# etchasketch.net
KiCad netlist of a schematic drawn in EAGLE
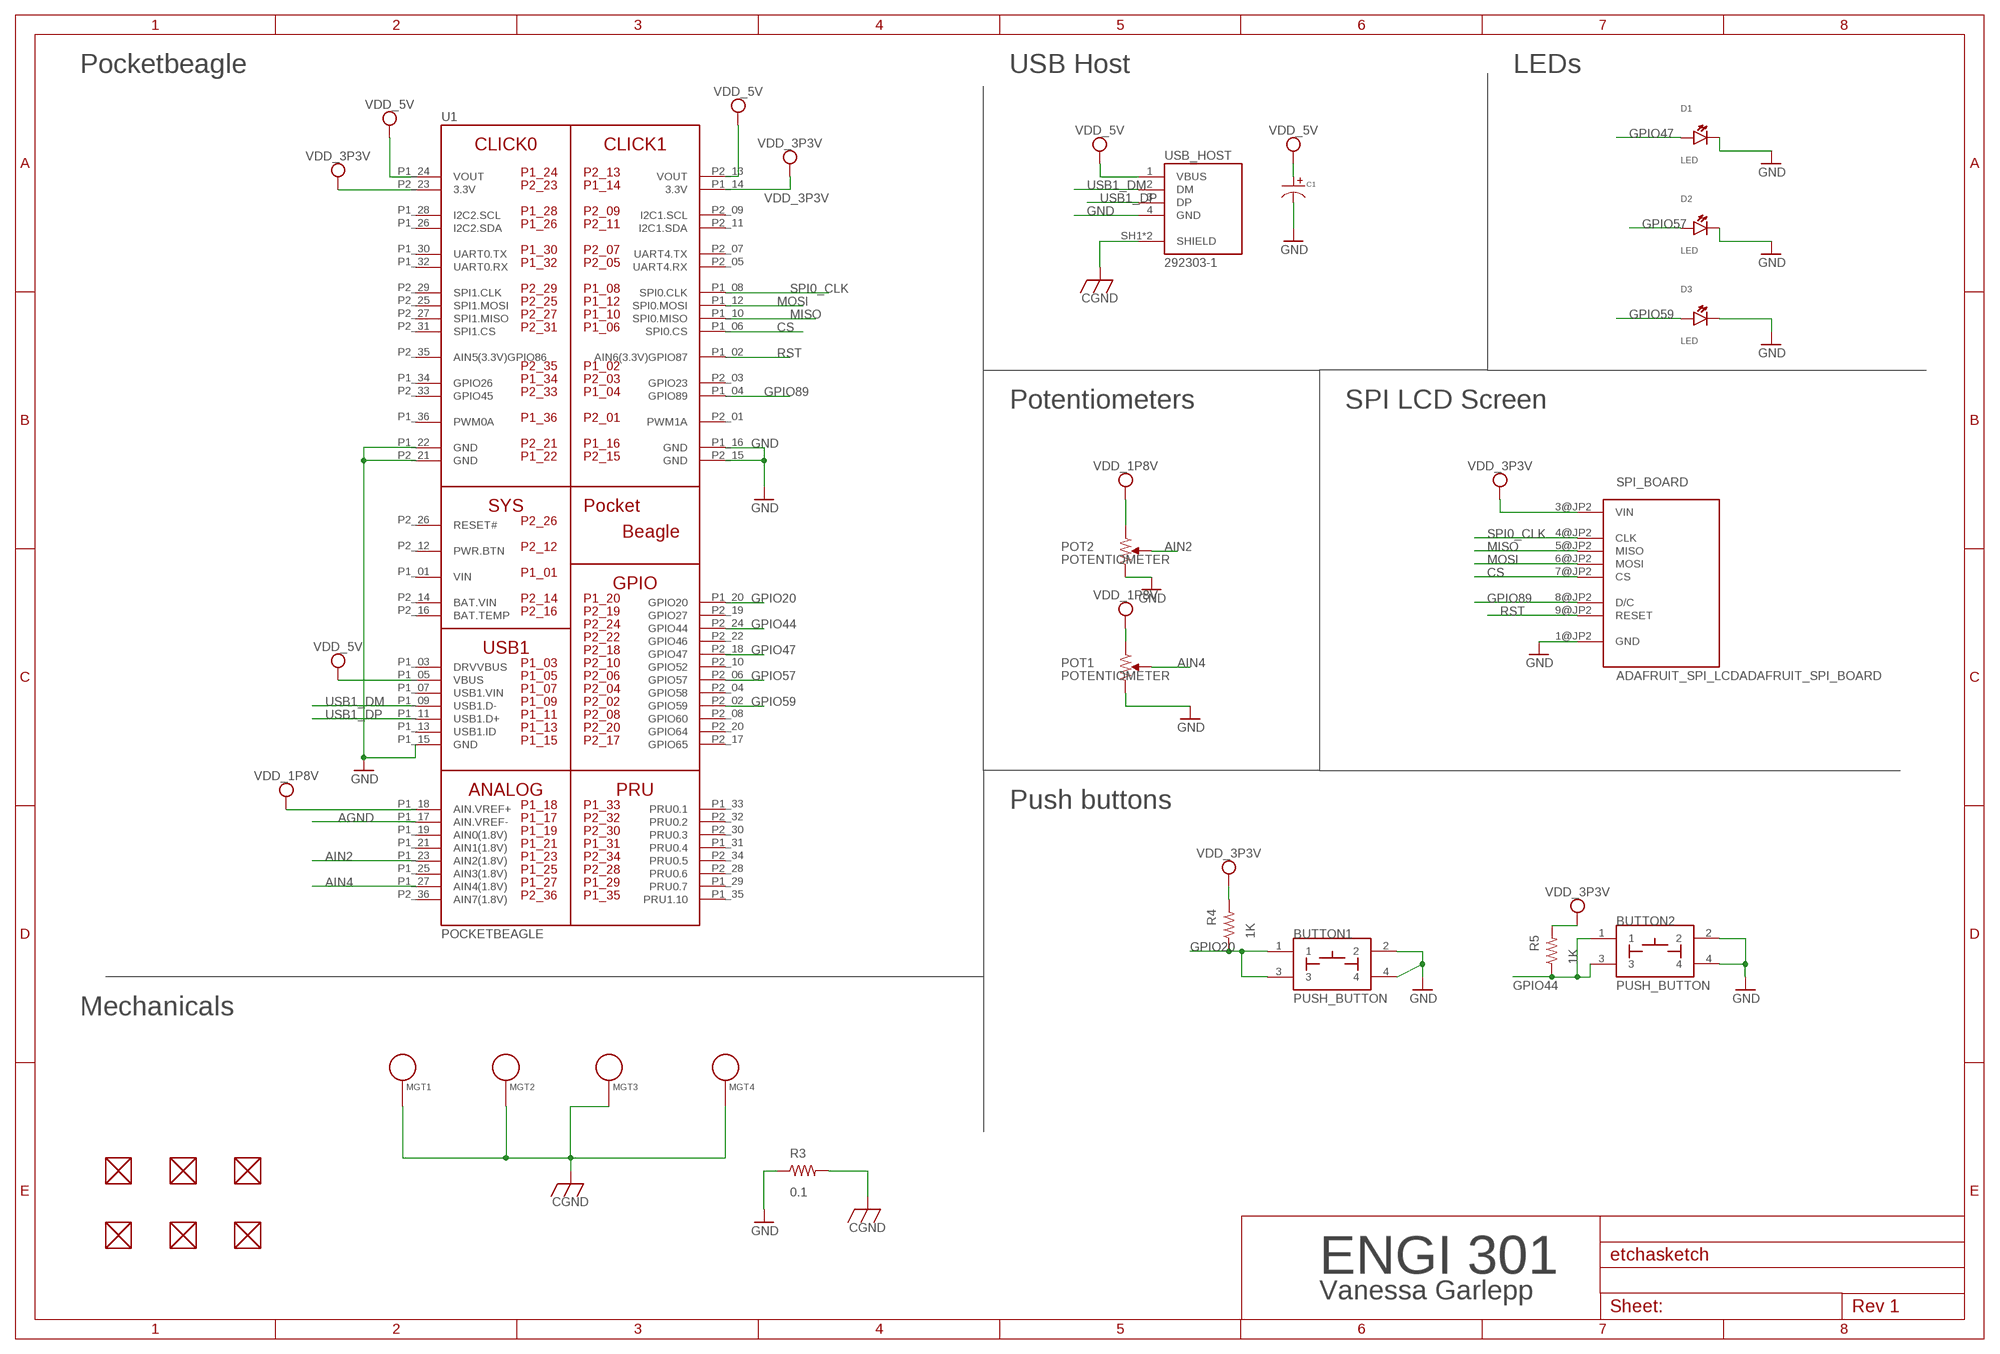
[diagram p0: schematic, sheet 1]

(export (version "E")
  (design (tool "Eeschema 10.0.6"))
  (components
    (comp (ref "BUTTON1")
      (value "PUSH_BUTTON")
      (footprint "eagle-import:BUTTON_12.5MM")
      (libsource (lib "eagle-import") (part "PUSH_BUTTON"))
    )
    (comp (ref "BUTTON2")
      (value "PUSH_BUTTON")
      (footprint "eagle-import:BUTTON_12.5MM")
      (libsource (lib "eagle-import") (part "PUSH_BUTTON"))
    )
    (comp (ref "C1")
      (value "CAPACITOR_P_10MM")
      (footprint "eagle-import:CP10MM")
      (libsource (lib "eagle-import") (part "CAPACITOR_P_10MM"))
    )
    (comp (ref "D1")
      (value "LED")
      (footprint "eagle-import:EIA-STD")
      (libsource (lib "eagle-import") (part "LED"))
    )
    (comp (ref "D2")
      (value "LED")
      (footprint "eagle-import:EIA-STD")
      (libsource (lib "eagle-import") (part "LED"))
    )
    (comp (ref "D3")
      (value "LED")
      (footprint "eagle-import:EIA-STD")
      (libsource (lib "eagle-import") (part "LED"))
    )
    (comp (ref "FUD1")
      (value "FIDUCIAL")
      (footprint "eagle-import:FIDUCIAL_40MIL")
      (libsource (lib "eagle-import") (part "FIDUCIAL"))
    )
    (comp (ref "FUD2")
      (value "FIDUCIAL")
      (footprint "eagle-import:FIDUCIAL_40MIL")
      (libsource (lib "eagle-import") (part "FIDUCIAL"))
    )
    (comp (ref "FUD3")
      (value "FIDUCIAL")
      (footprint "eagle-import:FIDUCIAL_40MIL")
      (libsource (lib "eagle-import") (part "FIDUCIAL"))
    )
    (comp (ref "FUD4")
      (value "FIDUCIAL")
      (footprint "eagle-import:FIDUCIAL_40MIL")
      (libsource (lib "eagle-import") (part "FIDUCIAL"))
    )
    (comp (ref "FUD5")
      (value "FIDUCIAL")
      (footprint "eagle-import:FIDUCIAL_40MIL")
      (libsource (lib "eagle-import") (part "FIDUCIAL"))
    )
    (comp (ref "FUD6")
      (value "FIDUCIAL")
      (footprint "eagle-import:FIDUCIAL_40MIL")
      (libsource (lib "eagle-import") (part "FIDUCIAL"))
    )
    (comp (ref "MGT1")
      (value "MOUNTING_HOLE")
      (footprint "eagle-import:MOUNTING_HOLE")
      (libsource (lib "eagle-import") (part "MOUNTING_HOLE"))
    )
    (comp (ref "MGT2")
      (value "MOUNTING_HOLE")
      (footprint "eagle-import:MOUNTING_HOLE")
      (libsource (lib "eagle-import") (part "MOUNTING_HOLE"))
    )
    (comp (ref "MGT3")
      (value "MOUNTING_HOLE")
      (footprint "eagle-import:MOUNTING_HOLE")
      (libsource (lib "eagle-import") (part "MOUNTING_HOLE"))
    )
    (comp (ref "MGT4")
      (value "MOUNTING_HOLE")
      (footprint "eagle-import:MOUNTING_HOLE")
      (libsource (lib "eagle-import") (part "MOUNTING_HOLE"))
    )
    (comp (ref "POT1")
      (value "POTENTIOMETER")
      (footprint "eagle-import:POT-PO90S")
      (libsource (lib "eagle-import") (part "POTENTIOMETER"))
    )
    (comp (ref "POT2")
      (value "POTENTIOMETER")
      (footprint "eagle-import:POT-PO90S")
      (libsource (lib "eagle-import") (part "POTENTIOMETER"))
    )
    (comp (ref "R3")
      (value "0.1")
      (footprint "eagle-import:R0603")
      (libsource (lib "eagle-import") (part "R_R0603"))
    )
    (comp (ref "R4")
      (value "1K")
      (footprint "eagle-import:R0402")
      (libsource (lib "eagle-import") (part "R_R0402"))
    )
    (comp (ref "R5")
      (value "1K")
      (footprint "eagle-import:R0402")
      (libsource (lib "eagle-import") (part "R_R0402"))
    )
    (comp (ref "SPI_BOARD")
      (value "ADAFRUIT_SPI_LCDADAFRUIT_SPI_BOARD")
      (footprint "eagle-import:ADAFRUIT_SPI_BOARD")
      (libsource (lib "eagle-import") (part "ADAFRUIT_SPI_LCDADAFRUIT_SPI_BOARD"))
    )
    (comp (ref "U1")
      (value "POCKETBEAGLE")
      (footprint "eagle-import:POCKETBEAGLE")
      (libsource (lib "eagle-import") (part "POCKETBEAGLE"))
    )
    (comp (ref "USB_HOST")
      (value "292303-1")
      (footprint "eagle-import:TE_292303-1")
      (fields (field (name "MF") "TE Connectivity"))
      (libsource (lib "eagle-import") (part "292303-1"))
    )
  )
  (nets
    (net (code "1") (name "/AGND") (class "Default")
      (node (ref "U1") (pin "P1_17") (pinfunction "AIN.VREF-_P1_17") (pintype "input"))
    )
    (net (code "2") (name "/AIN2") (class "Default")
      (node (ref "POT2") (pin "S") (pinfunction "S_S") (pintype "bidirectional"))
      (node (ref "U1") (pin "P1_23") (pinfunction "AIN2(1.8V)_P1_23") (pintype "input"))
    )
    (net (code "3") (name "/AIN4") (class "Default")
      (node (ref "POT1") (pin "S") (pinfunction "S_S") (pintype "bidirectional"))
      (node (ref "U1") (pin "P1_27") (pinfunction "AIN4(1.8V)_P1_27") (pintype "input"))
    )
    (net (code "4") (name "/BAT.VIN") (class "Default")
      (node (ref "U1") (pin "P2_14") (pinfunction "BAT.VIN_P2_14") (pintype "power_in"))
    )
    (net (code "5") (name "/CS") (class "Default")
      (node (ref "SPI_BOARD") (pin "7@JP2") (pinfunction "CS_7@JP2") (pintype "bidirectional"))
      (node (ref "U1") (pin "P1_06") (pinfunction "SPI0.CS_P1_06") (pintype "bidirectional"))
    )
    (net (code "6") (name "/GPIO20") (class "Default")
      (node (ref "BUTTON1") (pin "1") (pinfunction "1_1") (pintype "bidirectional"))
      (node (ref "BUTTON1") (pin "3") (pinfunction "3_3") (pintype "bidirectional"))
      (node (ref "R4") (pin "1") (pinfunction "1_1") (pintype "passive"))
      (node (ref "U1") (pin "P1_20") (pinfunction "GPIO20_P1_20") (pintype "bidirectional"))
    )
    (net (code "7") (name "/GPIO44") (class "Default")
      (node (ref "BUTTON2") (pin "1") (pinfunction "1_1") (pintype "bidirectional"))
      (node (ref "BUTTON2") (pin "3") (pinfunction "3_3") (pintype "bidirectional"))
      (node (ref "R5") (pin "1") (pinfunction "1_1") (pintype "passive"))
      (node (ref "U1") (pin "P2_24") (pinfunction "GPIO44_P2_24") (pintype "bidirectional"))
    )
    (net (code "8") (name "/GPIO47") (class "Default")
      (node (ref "D1") (pin "ANODE") (pinfunction "ANODE_ANODE") (pintype "bidirectional"))
      (node (ref "U1") (pin "P2_18") (pinfunction "GPIO47_P2_18") (pintype "bidirectional"))
    )
    (net (code "9") (name "/GPIO57") (class "Default")
      (node (ref "D2") (pin "ANODE") (pinfunction "ANODE_ANODE") (pintype "bidirectional"))
      (node (ref "U1") (pin "P2_06") (pinfunction "GPIO57_P2_06") (pintype "bidirectional"))
    )
    (net (code "10") (name "/GPIO59") (class "Default")
      (node (ref "D3") (pin "ANODE") (pinfunction "ANODE_ANODE") (pintype "bidirectional"))
      (node (ref "U1") (pin "P2_02") (pinfunction "GPIO59_P2_02") (pintype "bidirectional"))
    )
    (net (code "11") (name "/GPIO89") (class "Default")
      (node (ref "SPI_BOARD") (pin "8@JP2") (pinfunction "D/C_8@JP2") (pintype "bidirectional"))
      (node (ref "U1") (pin "P1_04") (pinfunction "GPIO89_P1_04") (pintype "bidirectional"))
    )
    (net (code "12") (name "/MISO") (class "Default")
      (node (ref "SPI_BOARD") (pin "5@JP2") (pinfunction "MISO_5@JP2") (pintype "bidirectional"))
      (node (ref "U1") (pin "P1_10") (pinfunction "SPI0.MISO_P1_10") (pintype "bidirectional"))
    )
    (net (code "13") (name "/MOSI") (class "Default")
      (node (ref "SPI_BOARD") (pin "6@JP2") (pinfunction "MOSI_6@JP2") (pintype "bidirectional"))
      (node (ref "U1") (pin "P1_12") (pinfunction "SPI0.MOSI_P1_12") (pintype "bidirectional"))
    )
    (net (code "14") (name "/RST") (class "Default")
      (node (ref "SPI_BOARD") (pin "9@JP2") (pinfunction "RESET_9@JP2") (pintype "bidirectional"))
      (node (ref "U1") (pin "P1_02") (pinfunction "AIN6(3.3V)GPIO87_P1_02") (pintype "bidirectional"))
    )
    (net (code "15") (name "/SPI0_CLK") (class "Default")
      (node (ref "SPI_BOARD") (pin "4@JP2") (pinfunction "CLK_4@JP2") (pintype "bidirectional"))
      (node (ref "U1") (pin "P1_08") (pinfunction "SPI0.CLK_P1_08") (pintype "bidirectional"))
    )
    (net (code "16") (name "/USB1_DM") (class "Default")
      (node (ref "U1") (pin "P1_09") (pinfunction "USB1.D-_P1_09") (pintype "bidirectional"))
      (node (ref "USB_HOST") (pin "2") (pinfunction "DM_2") (pintype "passive"))
    )
    (net (code "17") (name "/USB1_DP") (class "Default")
      (node (ref "U1") (pin "P1_11") (pinfunction "USB1.D+_P1_11") (pintype "bidirectional"))
      (node (ref "USB_HOST") (pin "3") (pinfunction "DP_3") (pintype "passive"))
    )
    (net (code "18") (name "/VIN") (class "Default")
      (node (ref "U1") (pin "P1_01") (pinfunction "VIN_P1_01") (pintype "power_in"))
    )
    (net (code "19") (name "CGND") (class "Default")
      (node (ref "MGT1") (pin "P$1") (pinfunction "P$1_P$1") (pintype "bidirectional"))
      (node (ref "MGT2") (pin "P$1") (pinfunction "P$1_P$1") (pintype "bidirectional"))
      (node (ref "MGT3") (pin "P$1") (pinfunction "P$1_P$1") (pintype "bidirectional"))
      (node (ref "MGT4") (pin "P$1") (pinfunction "P$1_P$1") (pintype "bidirectional"))
      (node (ref "R3") (pin "2") (pinfunction "2_2") (pintype "passive"))
      (node (ref "USB_HOST") (pin "SH1") (pinfunction "SHIELD_SH1") (pintype "passive"))
      (node (ref "USB_HOST") (pin "SH2") (pinfunction "SHIELD_SH2") (pintype "passive"))
    )
    (net (code "20") (name "GND") (class "Default")
      (node (ref "BUTTON1") (pin "2") (pinfunction "2_2") (pintype "bidirectional"))
      (node (ref "BUTTON1") (pin "4") (pinfunction "4_4") (pintype "bidirectional"))
      (node (ref "BUTTON2") (pin "2") (pinfunction "2_2") (pintype "bidirectional"))
      (node (ref "BUTTON2") (pin "4") (pinfunction "4_4") (pintype "bidirectional"))
      (node (ref "C1") (pin "P$2") (pinfunction "P$2_P$2") (pintype "passive"))
      (node (ref "D1") (pin "CATHODE") (pinfunction "CATHODE_CATHODE") (pintype "bidirectional"))
      (node (ref "D2") (pin "CATHODE") (pinfunction "CATHODE_CATHODE") (pintype "bidirectional"))
      (node (ref "D3") (pin "CATHODE") (pinfunction "CATHODE_CATHODE") (pintype "bidirectional"))
      (node (ref "POT1") (pin "CW") (pinfunction "CW_CW") (pintype "passive"))
      (node (ref "POT2") (pin "CW") (pinfunction "CW_CW") (pintype "passive"))
      (node (ref "R3") (pin "1") (pinfunction "1_1") (pintype "passive"))
      (node (ref "SPI_BOARD") (pin "1@JP2") (pinfunction "GND_1@JP2") (pintype "bidirectional"))
      (node (ref "U1") (pin "P1_15") (pinfunction "GND_P1_15") (pintype "bidirectional"))
      (node (ref "U1") (pin "P1_16") (pinfunction "GND_P1_16") (pintype "power_in"))
      (node (ref "U1") (pin "P1_22") (pinfunction "GND_P1_22") (pintype "power_in"))
      (node (ref "U1") (pin "P2_15") (pinfunction "GND_P2_15") (pintype "power_in"))
      (node (ref "U1") (pin "P2_21") (pinfunction "GND_P2_21") (pintype "power_in"))
      (node (ref "USB_HOST") (pin "4") (pinfunction "GND_4") (pintype "passive"))
    )
    (net (code "21") (name "VDD_1P8V") (class "Default")
      (node (ref "POT1") (pin "CCW") (pinfunction "CCW_CCW") (pintype "passive"))
      (node (ref "POT2") (pin "CCW") (pinfunction "CCW_CCW") (pintype "passive"))
      (node (ref "U1") (pin "P1_18") (pinfunction "AIN.VREF+_P1_18") (pintype "input"))
    )
    (net (code "22") (name "VDD_3P3V") (class "Default")
      (node (ref "R4") (pin "2") (pinfunction "2_2") (pintype "passive"))
      (node (ref "R5") (pin "2") (pinfunction "2_2") (pintype "passive"))
      (node (ref "SPI_BOARD") (pin "3@JP2") (pinfunction "VIN_3@JP2") (pintype "bidirectional"))
      (node (ref "U1") (pin "P1_14") (pinfunction "3.3V_P1_14") (pintype "power_in"))
      (node (ref "U1") (pin "P2_23") (pinfunction "3.3V_P2_23") (pintype "power_in"))
    )
    (net (code "23") (name "VDD_5V") (class "Default")
      (node (ref "C1") (pin "P$1") (pinfunction "P$1_P$1") (pintype "passive"))
      (node (ref "U1") (pin "P1_05") (pinfunction "VBUS_P1_05") (pintype "bidirectional"))
      (node (ref "U1") (pin "P1_24") (pinfunction "VOUT_P1_24") (pintype "power_in"))
      (node (ref "U1") (pin "P2_13") (pinfunction "VOUT_P2_13") (pintype "power_in"))
      (node (ref "USB_HOST") (pin "1") (pinfunction "VBUS_1") (pintype "passive"))
    )
    (net (code "24") (name "unconnected-(FUD1-PadP$1)") (class "Default")
      (node (ref "FUD1") (pin "P$1") (pinfunction "P$1_P$1") (pintype "no_connect"))
    )
    (net (code "25") (name "unconnected-(FUD2-PadP$1)") (class "Default")
      (node (ref "FUD2") (pin "P$1") (pinfunction "P$1_P$1") (pintype "no_connect"))
    )
    (net (code "26") (name "unconnected-(FUD3-PadP$1)") (class "Default")
      (node (ref "FUD3") (pin "P$1") (pinfunction "P$1_P$1") (pintype "no_connect"))
    )
    (net (code "27") (name "unconnected-(FUD4-PadP$1)") (class "Default")
      (node (ref "FUD4") (pin "P$1") (pinfunction "P$1_P$1") (pintype "no_connect"))
    )
    (net (code "28") (name "unconnected-(FUD5-PadP$1)") (class "Default")
      (node (ref "FUD5") (pin "P$1") (pinfunction "P$1_P$1") (pintype "no_connect"))
    )
    (net (code "29") (name "unconnected-(FUD6-PadP$1)") (class "Default")
      (node (ref "FUD6") (pin "P$1") (pinfunction "P$1_P$1") (pintype "no_connect"))
    )
    (net (code "30") (name "unconnected-(U1-AIN0(1.8V)-PadP1_19)") (class "Default")
      (node (ref "U1") (pin "P1_19") (pinfunction "AIN0(1.8V)_P1_19") (pintype "input"))
    )
    (net (code "31") (name "unconnected-(U1-AIN1(1.8V)-PadP1_21)") (class "Default")
      (node (ref "U1") (pin "P1_21") (pinfunction "AIN1(1.8V)_P1_21") (pintype "input"))
    )
    (net (code "32") (name "unconnected-(U1-AIN3(1.8V)-PadP1_25)") (class "Default")
      (node (ref "U1") (pin "P1_25") (pinfunction "AIN3(1.8V)_P1_25") (pintype "input"))
    )
    (net (code "33") (name "unconnected-(U1-AIN5(3.3V)GPIO86-PadP2_35)") (class "Default")
      (node (ref "U1") (pin "P2_35") (pinfunction "AIN5(3.3V)GPIO86_P2_35") (pintype "bidirectional"))
    )
    (net (code "34") (name "unconnected-(U1-AIN7(1.8V)-PadP2_36)") (class "Default")
      (node (ref "U1") (pin "P2_36") (pinfunction "AIN7(1.8V)_P2_36") (pintype "input"))
    )
    (net (code "35") (name "unconnected-(U1-BAT.TEMP-PadP2_16)") (class "Default")
      (node (ref "U1") (pin "P2_16") (pinfunction "BAT.TEMP_P2_16") (pintype "input"))
    )
    (net (code "36") (name "unconnected-(U1-DRVVBUS-PadP1_03)") (class "Default")
      (node (ref "U1") (pin "P1_03") (pinfunction "DRVVBUS_P1_03") (pintype "bidirectional"))
    )
    (net (code "37") (name "unconnected-(U1-GPIO23-PadP2_03)") (class "Default")
      (node (ref "U1") (pin "P2_03") (pinfunction "GPIO23_P2_03") (pintype "bidirectional"))
    )
    (net (code "38") (name "unconnected-(U1-GPIO26-PadP1_34)") (class "Default")
      (node (ref "U1") (pin "P1_34") (pinfunction "GPIO26_P1_34") (pintype "bidirectional"))
    )
    (net (code "39") (name "unconnected-(U1-GPIO27-PadP2_19)") (class "Default")
      (node (ref "U1") (pin "P2_19") (pinfunction "GPIO27_P2_19") (pintype "bidirectional"))
    )
    (net (code "40") (name "unconnected-(U1-GPIO45-PadP2_33)") (class "Default")
      (node (ref "U1") (pin "P2_33") (pinfunction "GPIO45_P2_33") (pintype "bidirectional"))
    )
    (net (code "41") (name "unconnected-(U1-GPIO46-PadP2_22)") (class "Default")
      (node (ref "U1") (pin "P2_22") (pinfunction "GPIO46_P2_22") (pintype "bidirectional"))
    )
    (net (code "42") (name "unconnected-(U1-GPIO52-PadP2_10)") (class "Default")
      (node (ref "U1") (pin "P2_10") (pinfunction "GPIO52_P2_10") (pintype "bidirectional"))
    )
    (net (code "43") (name "unconnected-(U1-GPIO58-PadP2_04)") (class "Default")
      (node (ref "U1") (pin "P2_04") (pinfunction "GPIO58_P2_04") (pintype "bidirectional"))
    )
    (net (code "44") (name "unconnected-(U1-GPIO60-PadP2_08)") (class "Default")
      (node (ref "U1") (pin "P2_08") (pinfunction "GPIO60_P2_08") (pintype "bidirectional"))
    )
    (net (code "45") (name "unconnected-(U1-GPIO64-PadP2_20)") (class "Default")
      (node (ref "U1") (pin "P2_20") (pinfunction "GPIO64_P2_20") (pintype "bidirectional"))
    )
    (net (code "46") (name "unconnected-(U1-GPIO65-PadP2_17)") (class "Default")
      (node (ref "U1") (pin "P2_17") (pinfunction "GPIO65_P2_17") (pintype "bidirectional"))
    )
    (net (code "47") (name "unconnected-(U1-I2C1.SCL-PadP2_09)") (class "Default")
      (node (ref "U1") (pin "P2_09") (pinfunction "I2C1.SCL_P2_09") (pintype "bidirectional"))
    )
    (net (code "48") (name "unconnected-(U1-I2C1.SDA-PadP2_11)") (class "Default")
      (node (ref "U1") (pin "P2_11") (pinfunction "I2C1.SDA_P2_11") (pintype "bidirectional"))
    )
    (net (code "49") (name "unconnected-(U1-I2C2.SCL-PadP1_28)") (class "Default")
      (node (ref "U1") (pin "P1_28") (pinfunction "I2C2.SCL_P1_28") (pintype "bidirectional"))
    )
    (net (code "50") (name "unconnected-(U1-I2C2.SDA-PadP1_26)") (class "Default")
      (node (ref "U1") (pin "P1_26") (pinfunction "I2C2.SDA_P1_26") (pintype "bidirectional"))
    )
    (net (code "51") (name "unconnected-(U1-PRU0.1-PadP1_33)") (class "Default")
      (node (ref "U1") (pin "P1_33") (pinfunction "PRU0.1_P1_33") (pintype "bidirectional"))
    )
    (net (code "52") (name "unconnected-(U1-PRU0.2-PadP2_32)") (class "Default")
      (node (ref "U1") (pin "P2_32") (pinfunction "PRU0.2_P2_32") (pintype "bidirectional"))
    )
    (net (code "53") (name "unconnected-(U1-PRU0.3-PadP2_30)") (class "Default")
      (node (ref "U1") (pin "P2_30") (pinfunction "PRU0.3_P2_30") (pintype "bidirectional"))
    )
    (net (code "54") (name "unconnected-(U1-PRU0.4-PadP1_31)") (class "Default")
      (node (ref "U1") (pin "P1_31") (pinfunction "PRU0.4_P1_31") (pintype "bidirectional"))
    )
    (net (code "55") (name "unconnected-(U1-PRU0.5-PadP2_34)") (class "Default")
      (node (ref "U1") (pin "P2_34") (pinfunction "PRU0.5_P2_34") (pintype "bidirectional"))
    )
    (net (code "56") (name "unconnected-(U1-PRU0.6-PadP2_28)") (class "Default")
      (node (ref "U1") (pin "P2_28") (pinfunction "PRU0.6_P2_28") (pintype "bidirectional"))
    )
    (net (code "57") (name "unconnected-(U1-PRU0.7-PadP1_29)") (class "Default")
      (node (ref "U1") (pin "P1_29") (pinfunction "PRU0.7_P1_29") (pintype "bidirectional"))
    )
    (net (code "58") (name "unconnected-(U1-PRU1.10-PadP1_35)") (class "Default")
      (node (ref "U1") (pin "P1_35") (pinfunction "PRU1.10_P1_35") (pintype "bidirectional"))
    )
    (net (code "59") (name "unconnected-(U1-PWM0A-PadP1_36)") (class "Default")
      (node (ref "U1") (pin "P1_36") (pinfunction "PWM0A_P1_36") (pintype "bidirectional"))
    )
    (net (code "60") (name "unconnected-(U1-PWM1A-PadP2_01)") (class "Default")
      (node (ref "U1") (pin "P2_01") (pinfunction "PWM1A_P2_01") (pintype "bidirectional"))
    )
    (net (code "61") (name "unconnected-(U1-PWR.BTN-PadP2_12)") (class "Default")
      (node (ref "U1") (pin "P2_12") (pinfunction "PWR.BTN_P2_12") (pintype "input"))
    )
    (net (code "62") (name "unconnected-(U1-RESET#-PadP2_26)") (class "Default")
      (node (ref "U1") (pin "P2_26") (pinfunction "RESET#_P2_26") (pintype "input"))
    )
    (net (code "63") (name "unconnected-(U1-SPI1.CLK-PadP2_29)") (class "Default")
      (node (ref "U1") (pin "P2_29") (pinfunction "SPI1.CLK_P2_29") (pintype "bidirectional"))
    )
    (net (code "64") (name "unconnected-(U1-SPI1.CS-PadP2_31)") (class "Default")
      (node (ref "U1") (pin "P2_31") (pinfunction "SPI1.CS_P2_31") (pintype "bidirectional"))
    )
    (net (code "65") (name "unconnected-(U1-SPI1.MISO-PadP2_27)") (class "Default")
      (node (ref "U1") (pin "P2_27") (pinfunction "SPI1.MISO_P2_27") (pintype "bidirectional"))
    )
    (net (code "66") (name "unconnected-(U1-SPI1.MOSI-PadP2_25)") (class "Default")
      (node (ref "U1") (pin "P2_25") (pinfunction "SPI1.MOSI_P2_25") (pintype "bidirectional"))
    )
    (net (code "67") (name "unconnected-(U1-UART0.RX-PadP1_32)") (class "Default")
      (node (ref "U1") (pin "P1_32") (pinfunction "UART0.RX_P1_32") (pintype "bidirectional"))
    )
    (net (code "68") (name "unconnected-(U1-UART0.TX-PadP1_30)") (class "Default")
      (node (ref "U1") (pin "P1_30") (pinfunction "UART0.TX_P1_30") (pintype "bidirectional"))
    )
    (net (code "69") (name "unconnected-(U1-UART4.RX-PadP2_05)") (class "Default")
      (node (ref "U1") (pin "P2_05") (pinfunction "UART4.RX_P2_05") (pintype "bidirectional"))
    )
    (net (code "70") (name "unconnected-(U1-UART4.TX-PadP2_07)") (class "Default")
      (node (ref "U1") (pin "P2_07") (pinfunction "UART4.TX_P2_07") (pintype "bidirectional"))
    )
    (net (code "71") (name "unconnected-(U1-USB1.ID-PadP1_13)") (class "Default")
      (node (ref "U1") (pin "P1_13") (pinfunction "USB1.ID_P1_13") (pintype "bidirectional"))
    )
    (net (code "72") (name "unconnected-(U1-USB1.VIN-PadP1_07)") (class "Default")
      (node (ref "U1") (pin "P1_07") (pinfunction "USB1.VIN_P1_07") (pintype "bidirectional"))
    )
  )
)
